# mrShark_08.net
KiCad netlist of a schematic drawn in EAGLE
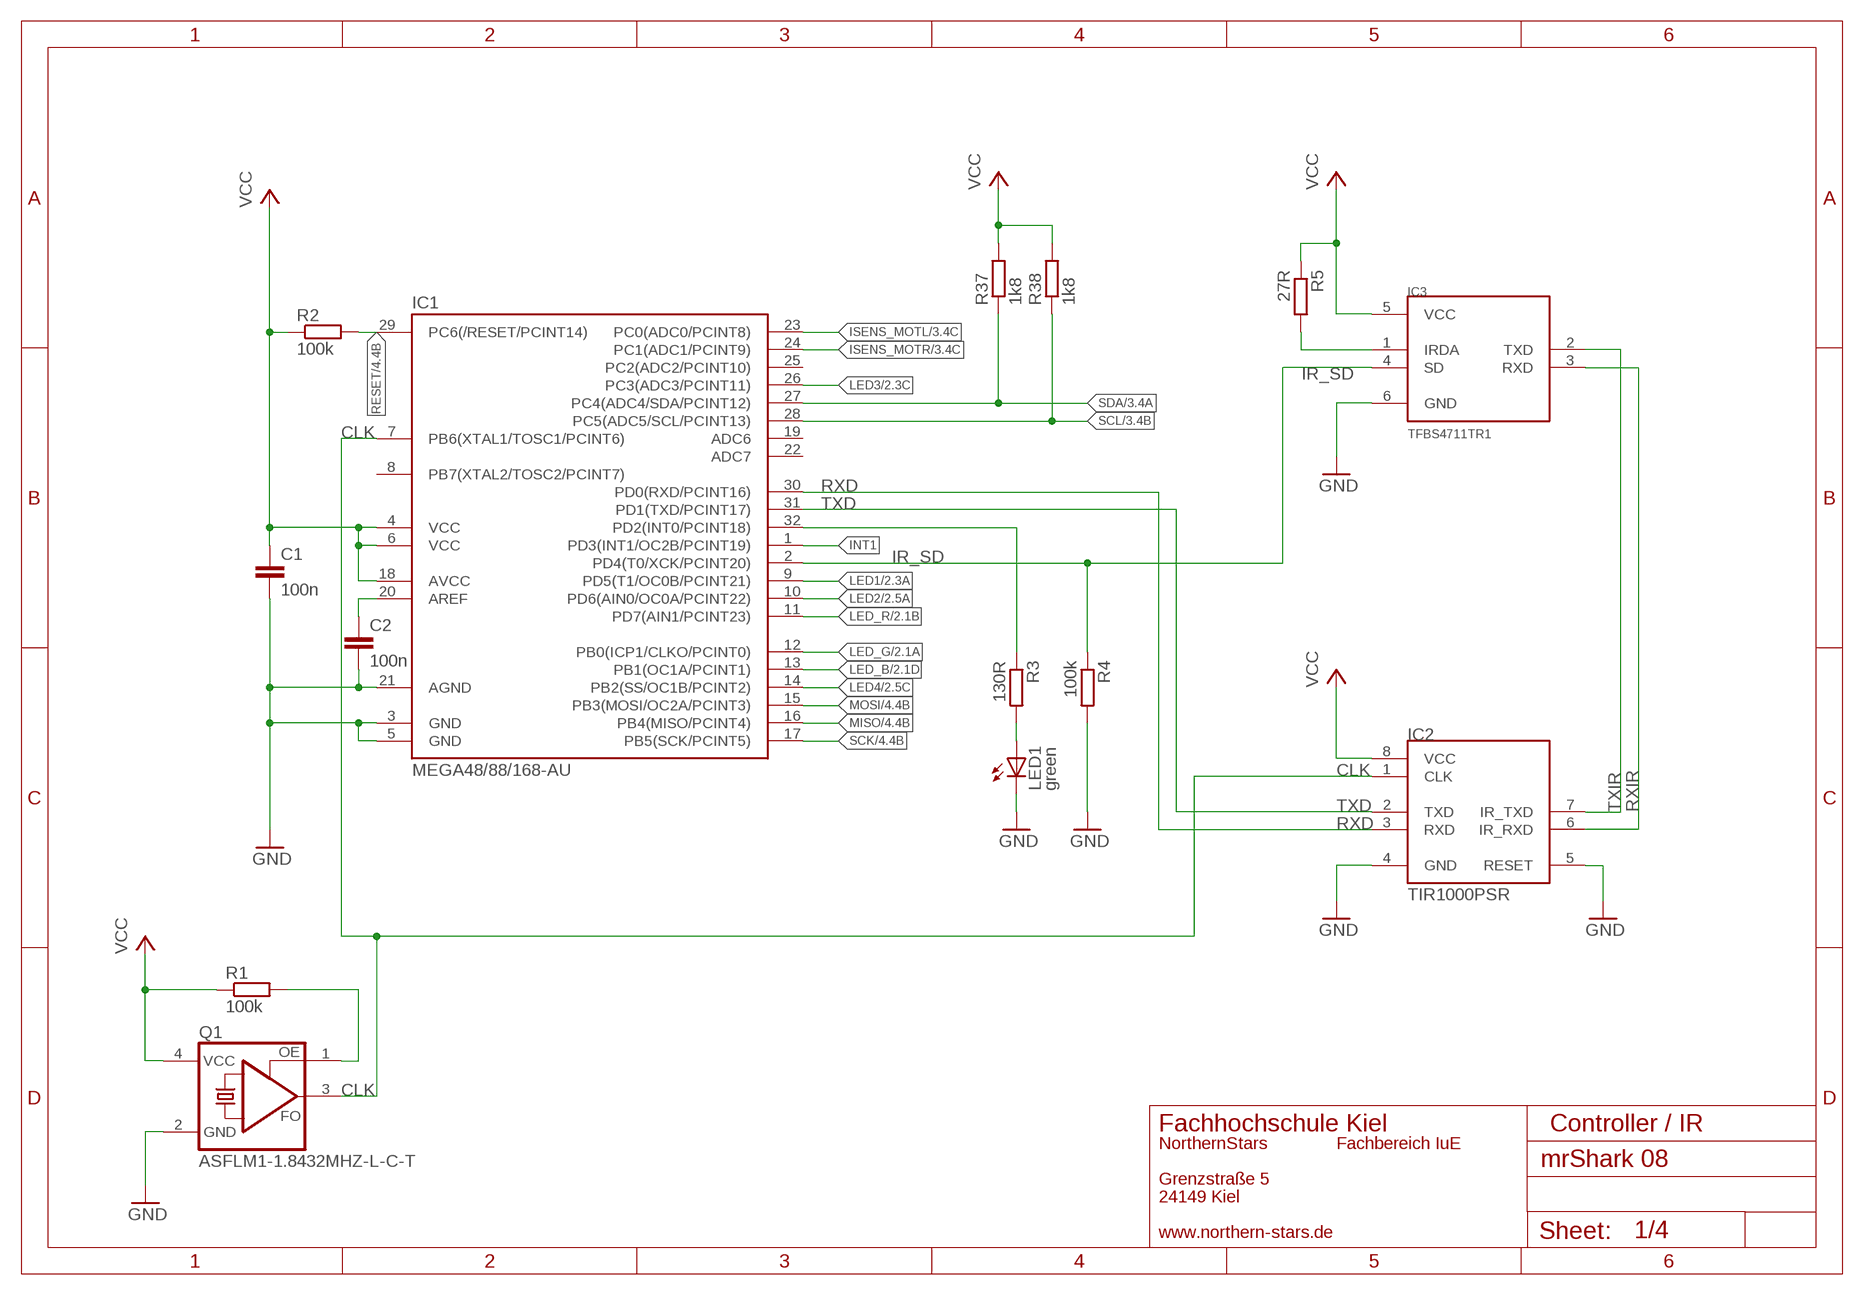
[diagram p0: schematic, sheet 1]
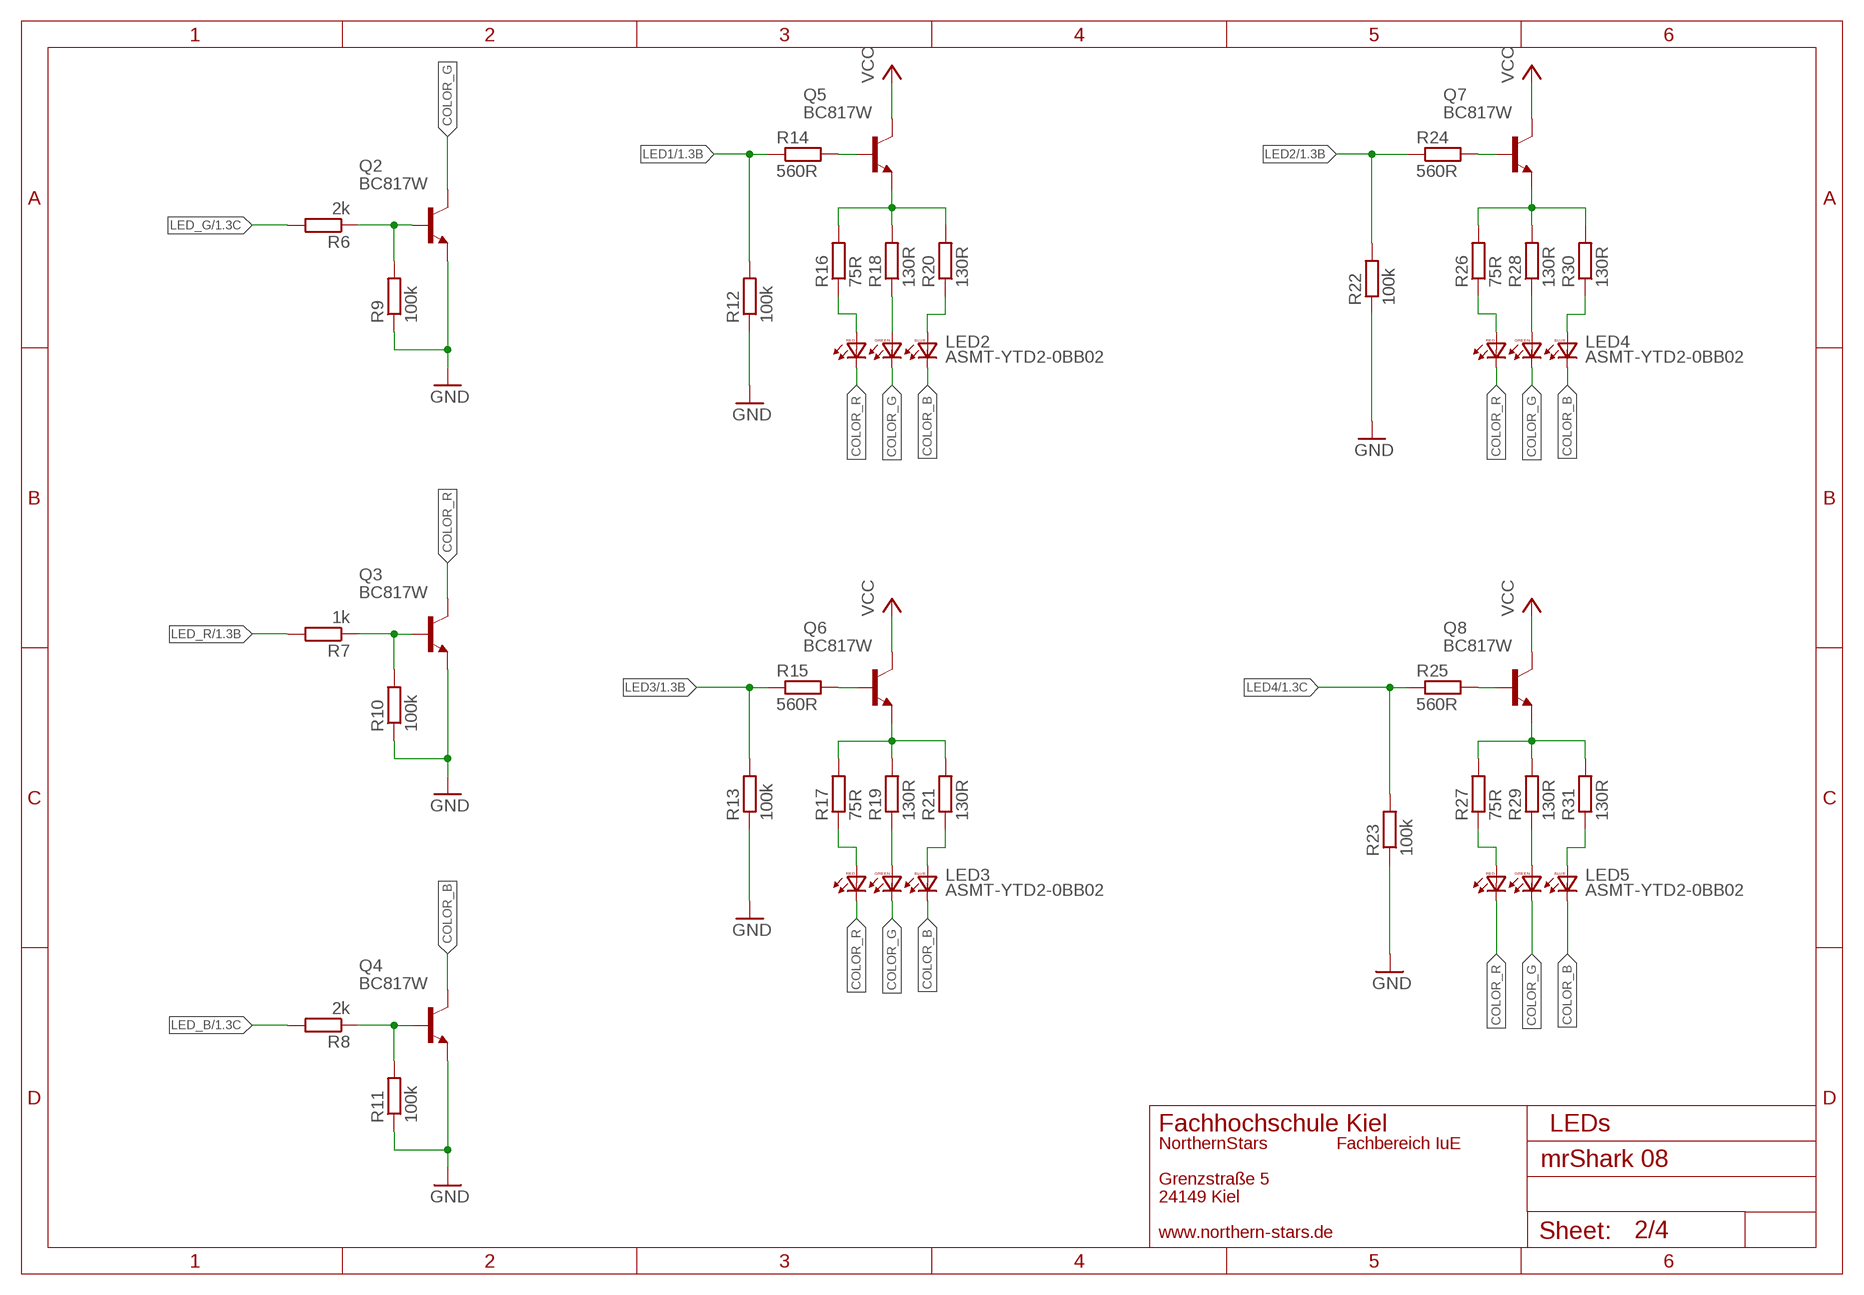
[diagram p1: schematic, sheet 2]
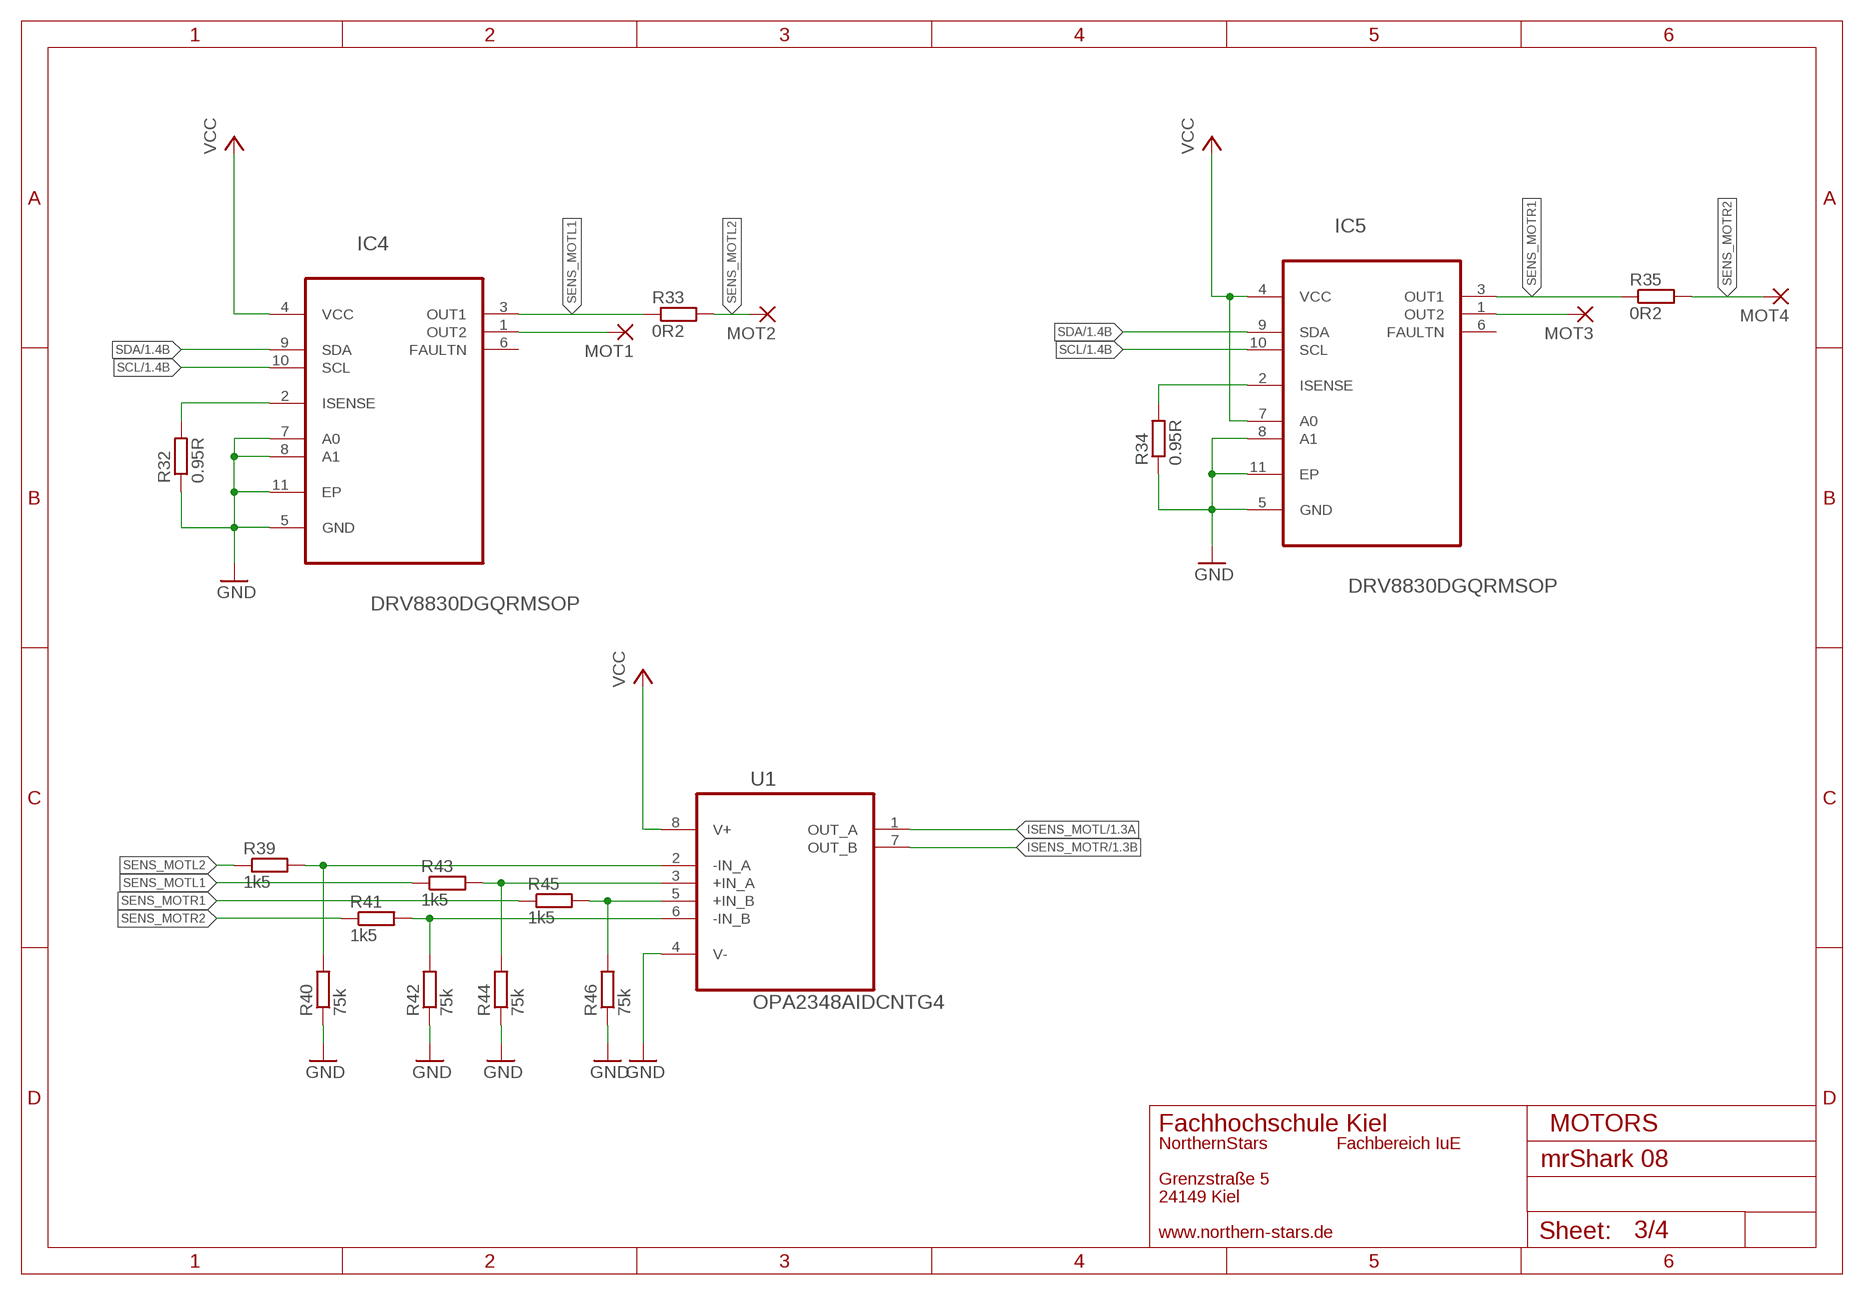
[diagram p2: schematic, sheet 3]
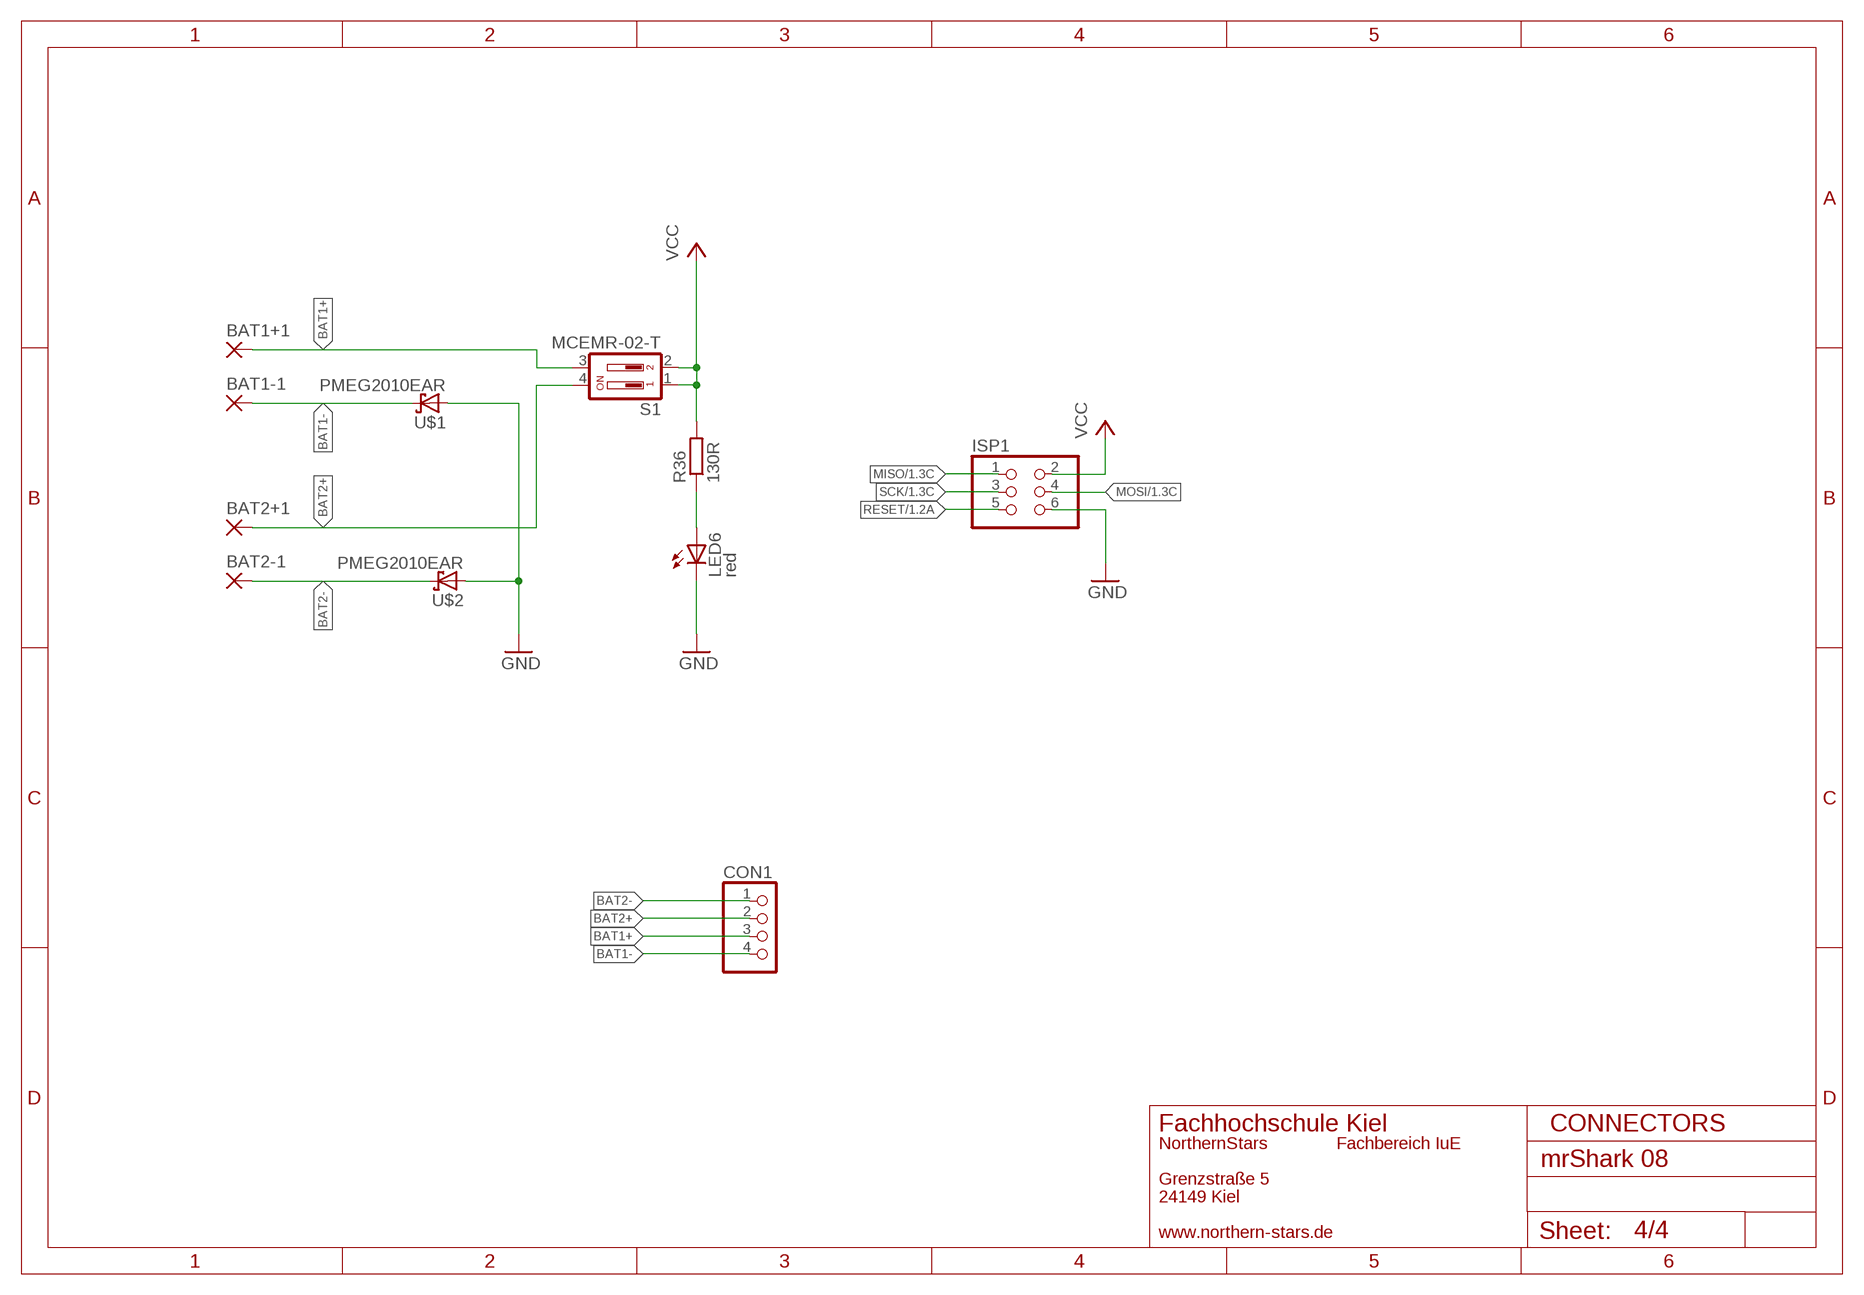
[diagram p3: schematic, sheet 4]

(export (version "E")
  (design (tool "Eeschema 10.0.6"))
  (components
    (comp (ref "IC4")
      (value "DRV8830DGQRMSOP")
      (footprint "eagle-import:SOP65P640X110-15N")
      (fields (field (name "MPN") "DRV8830DGQR"))
      (libsource (lib "eagle-import") (part "DRV8830DGQRMSOP"))
    )
    (comp (ref "IC5")
      (value "DRV8830DGQRMSOP")
      (footprint "eagle-import:SOP65P640X110-15N")
      (fields (field (name "MPN") "DRV8830DGQR"))
      (libsource (lib "eagle-import") (part "DRV8830DGQRMSOP"))
    )
    (comp (ref "MOT1")
      (value "1,6/0,9")
      (footprint "eagle-import:1,6_0,9")
      (libsource (lib "eagle-import") (part "1,6/0,9"))
    )
    (comp (ref "MOT2")
      (value "1,6/0,9")
      (footprint "eagle-import:1,6_0,9")
      (libsource (lib "eagle-import") (part "1,6/0,9"))
    )
    (comp (ref "MOT3")
      (value "1,6/0,9")
      (footprint "eagle-import:1,6_0,9")
      (libsource (lib "eagle-import") (part "1,6/0,9"))
    )
    (comp (ref "MOT4")
      (value "1,6/0,9")
      (footprint "eagle-import:1,6_0,9")
      (libsource (lib "eagle-import") (part "1,6/0,9"))
    )
    (comp (ref "R32")
      (value "0.95R")
      (footprint "eagle-import:R1206")
      (libsource (lib "eagle-import") (part "R-EU_R1206"))
    )
    (comp (ref "R33")
      (value "0R2")
      (footprint "eagle-import:R0805")
      (libsource (lib "eagle-import") (part "R-EU_R0805"))
    )
    (comp (ref "R34")
      (value "0.95R")
      (footprint "eagle-import:R1206")
      (libsource (lib "eagle-import") (part "R-EU_R1206"))
    )
    (comp (ref "R35")
      (value "0R2")
      (footprint "eagle-import:R0805")
      (libsource (lib "eagle-import") (part "R-EU_R0805"))
    )
    (comp (ref "R39")
      (value "1k5")
      (footprint "eagle-import:R1206")
      (libsource (lib "eagle-import") (part "R-EU_R1206"))
    )
    (comp (ref "R40")
      (value "75k")
      (footprint "eagle-import:R1206")
      (libsource (lib "eagle-import") (part "R-EU_R1206"))
    )
    (comp (ref "R41")
      (value "1k5")
      (footprint "eagle-import:R1206")
      (libsource (lib "eagle-import") (part "R-EU_R1206"))
    )
    (comp (ref "R42")
      (value "75k")
      (footprint "eagle-import:R1206")
      (libsource (lib "eagle-import") (part "R-EU_R1206"))
    )
    (comp (ref "R43")
      (value "1k5")
      (footprint "eagle-import:R1206")
      (libsource (lib "eagle-import") (part "R-EU_R1206"))
    )
    (comp (ref "R44")
      (value "75k")
      (footprint "eagle-import:R1206")
      (libsource (lib "eagle-import") (part "R-EU_R1206"))
    )
    (comp (ref "R45")
      (value "1k5")
      (footprint "eagle-import:R1206")
      (libsource (lib "eagle-import") (part "R-EU_R1206"))
    )
    (comp (ref "R46")
      (value "75k")
      (footprint "eagle-import:R1206")
      (libsource (lib "eagle-import") (part "R-EU_R1206"))
    )
    (comp (ref "U1")
      (value "OPA2348AIDCNTG4")
      (footprint "eagle-import:SOT65P280X145-8N")
      (libsource (lib "eagle-import") (part "OPA2348AIDCNTG4"))
    )
    (comp (ref "C1")
      (value "100n")
      (footprint "eagle-import:C0805")
      (libsource (lib "eagle-import") (part "C-EUC0805"))
    )
    (comp (ref "C2")
      (value "100n")
      (footprint "eagle-import:C0805")
      (libsource (lib "eagle-import") (part "C-EUC0805"))
    )
    (comp (ref "IC1")
      (value "MEGA48/88/168-AU")
      (footprint "eagle-import:TQFP32-08")
      (libsource (lib "eagle-import") (part "MEGA48/88/168-AU"))
    )
    (comp (ref "IC2")
      (value "TIR1000PSR")
      (footprint "eagle-import:SO-08")
      (libsource (lib "eagle-import") (part "TIR1000PSR"))
    )
    (comp (ref "IC3")
      (value "TFBS4711TR1")
      (footprint "eagle-import:TFBS4711")
      (libsource (lib "eagle-import") (part "TFBS4711TR1"))
    )
    (comp (ref "LED1")
      (value "green")
      (footprint "eagle-import:CHIPLED_1206")
      (libsource (lib "eagle-import") (part "LEDCHIPLED_1206"))
    )
    (comp (ref "Q1")
      (value "ASFLM1-1.8432MHZ-L-C-T")
      (footprint "eagle-import:HC736")
      (libsource (lib "eagle-import") (part "HC536(738)"))
    )
    (comp (ref "R1")
      (value "100k")
      (footprint "eagle-import:R1206")
      (libsource (lib "eagle-import") (part "R-EU_R1206"))
    )
    (comp (ref "R2")
      (value "100k")
      (footprint "eagle-import:R1206")
      (libsource (lib "eagle-import") (part "R-EU_R1206"))
    )
    (comp (ref "R3")
      (value "130R")
      (footprint "eagle-import:R1206")
      (libsource (lib "eagle-import") (part "R-EU_R1206"))
    )
    (comp (ref "R4")
      (value "100k")
      (footprint "eagle-import:R1206")
      (libsource (lib "eagle-import") (part "R-EU_R1206"))
    )
    (comp (ref "R5")
      (value "27R")
      (footprint "eagle-import:R1206")
      (libsource (lib "eagle-import") (part "R-EU_R1206"))
    )
    (comp (ref "R37")
      (value "1k8")
      (footprint "eagle-import:R1206")
      (libsource (lib "eagle-import") (part "R-EU_R1206"))
    )
    (comp (ref "R38")
      (value "1k8")
      (footprint "eagle-import:R1206")
      (libsource (lib "eagle-import") (part "R-EU_R1206"))
    )
    (comp (ref "LED2")
      (value "ASMT-YTD2-0BB02")
      (footprint "eagle-import:PLCC6K")
      (libsource (lib "eagle-import") (part "PLCC6K"))
    )
    (comp (ref "LED3")
      (value "ASMT-YTD2-0BB02")
      (footprint "eagle-import:PLCC6K")
      (libsource (lib "eagle-import") (part "PLCC6K"))
    )
    (comp (ref "LED4")
      (value "ASMT-YTD2-0BB02")
      (footprint "eagle-import:PLCC6K")
      (libsource (lib "eagle-import") (part "PLCC6K"))
    )
    (comp (ref "LED5")
      (value "ASMT-YTD2-0BB02")
      (footprint "eagle-import:PLCC6K")
      (libsource (lib "eagle-import") (part "PLCC6K"))
    )
    (comp (ref "Q2")
      (value "BC817W")
      (footprint "eagle-import:SOT323-BEC")
      (libsource (lib "eagle-import") (part "BC817W"))
    )
    (comp (ref "Q3")
      (value "BC817W")
      (footprint "eagle-import:SOT323-BEC")
      (libsource (lib "eagle-import") (part "BC817W"))
    )
    (comp (ref "Q4")
      (value "BC817W")
      (footprint "eagle-import:SOT323-BEC")
      (libsource (lib "eagle-import") (part "BC817W"))
    )
    (comp (ref "Q5")
      (value "BC817W")
      (footprint "eagle-import:SOT323-BEC")
      (libsource (lib "eagle-import") (part "BC817W"))
    )
    (comp (ref "Q6")
      (value "BC817W")
      (footprint "eagle-import:SOT323-BEC")
      (libsource (lib "eagle-import") (part "BC817W"))
    )
    (comp (ref "Q7")
      (value "BC817W")
      (footprint "eagle-import:SOT323-BEC")
      (libsource (lib "eagle-import") (part "BC817W"))
    )
    (comp (ref "Q8")
      (value "BC817W")
      (footprint "eagle-import:SOT323-BEC")
      (libsource (lib "eagle-import") (part "BC817W"))
    )
    (comp (ref "R6")
      (value "2k")
      (footprint "eagle-import:R1206")
      (libsource (lib "eagle-import") (part "R-EU_R1206"))
    )
    (comp (ref "R7")
      (value "1k")
      (footprint "eagle-import:R1206")
      (libsource (lib "eagle-import") (part "R-EU_R1206"))
    )
    (comp (ref "R8")
      (value "2k")
      (footprint "eagle-import:R1206")
      (libsource (lib "eagle-import") (part "R-EU_R1206"))
    )
    (comp (ref "R9")
      (value "100k")
      (footprint "eagle-import:R1206")
      (libsource (lib "eagle-import") (part "R-EU_R1206"))
    )
    (comp (ref "R10")
      (value "100k")
      (footprint "eagle-import:R1206")
      (libsource (lib "eagle-import") (part "R-EU_R1206"))
    )
    (comp (ref "R11")
      (value "100k")
      (footprint "eagle-import:R1206")
      (libsource (lib "eagle-import") (part "R-EU_R1206"))
    )
    (comp (ref "R12")
      (value "100k")
      (footprint "eagle-import:R1206")
      (libsource (lib "eagle-import") (part "R-EU_R1206"))
    )
    (comp (ref "R13")
      (value "100k")
      (footprint "eagle-import:R1206")
      (libsource (lib "eagle-import") (part "R-EU_R1206"))
    )
    (comp (ref "R14")
      (value "560R")
      (footprint "eagle-import:R1206")
      (libsource (lib "eagle-import") (part "R-EU_R1206"))
    )
    (comp (ref "R15")
      (value "560R")
      (footprint "eagle-import:R1206")
      (libsource (lib "eagle-import") (part "R-EU_R1206"))
    )
    (comp (ref "R16")
      (value "75R")
      (footprint "eagle-import:R1206")
      (libsource (lib "eagle-import") (part "R-EU_R1206"))
    )
    (comp (ref "R17")
      (value "75R")
      (footprint "eagle-import:R1206")
      (libsource (lib "eagle-import") (part "R-EU_R1206"))
    )
    (comp (ref "R18")
      (value "130R")
      (footprint "eagle-import:R1206")
      (libsource (lib "eagle-import") (part "R-EU_R1206"))
    )
    (comp (ref "R19")
      (value "130R")
      (footprint "eagle-import:R1206")
      (libsource (lib "eagle-import") (part "R-EU_R1206"))
    )
    (comp (ref "R20")
      (value "130R")
      (footprint "eagle-import:R1206")
      (libsource (lib "eagle-import") (part "R-EU_R1206"))
    )
    (comp (ref "R21")
      (value "130R")
      (footprint "eagle-import:R1206")
      (libsource (lib "eagle-import") (part "R-EU_R1206"))
    )
    (comp (ref "R22")
      (value "100k")
      (footprint "eagle-import:R1206")
      (libsource (lib "eagle-import") (part "R-EU_R1206"))
    )
    (comp (ref "R23")
      (value "100k")
      (footprint "eagle-import:R1206")
      (libsource (lib "eagle-import") (part "R-EU_R1206"))
    )
    (comp (ref "R24")
      (value "560R")
      (footprint "eagle-import:R1206")
      (libsource (lib "eagle-import") (part "R-EU_R1206"))
    )
    (comp (ref "R25")
      (value "560R")
      (footprint "eagle-import:R1206")
      (libsource (lib "eagle-import") (part "R-EU_R1206"))
    )
    (comp (ref "R26")
      (value "75R")
      (footprint "eagle-import:R1206")
      (libsource (lib "eagle-import") (part "R-EU_R1206"))
    )
    (comp (ref "R27")
      (value "75R")
      (footprint "eagle-import:R1206")
      (libsource (lib "eagle-import") (part "R-EU_R1206"))
    )
    (comp (ref "R28")
      (value "130R")
      (footprint "eagle-import:R1206")
      (libsource (lib "eagle-import") (part "R-EU_R1206"))
    )
    (comp (ref "R29")
      (value "130R")
      (footprint "eagle-import:R1206")
      (libsource (lib "eagle-import") (part "R-EU_R1206"))
    )
    (comp (ref "R30")
      (value "130R")
      (footprint "eagle-import:R1206")
      (libsource (lib "eagle-import") (part "R-EU_R1206"))
    )
    (comp (ref "R31")
      (value "130R")
      (footprint "eagle-import:R1206")
      (libsource (lib "eagle-import") (part "R-EU_R1206"))
    )
    (comp (ref "BAT1+1")
      (value "1,6/0,9")
      (footprint "eagle-import:1,6_0,9")
      (libsource (lib "eagle-import") (part "1,6/0,9"))
    )
    (comp (ref "BAT1-1")
      (value "1,6/0,9")
      (footprint "eagle-import:1,6_0,9")
      (libsource (lib "eagle-import") (part "1,6/0,9"))
    )
    (comp (ref "BAT2+1")
      (value "1,6/0,9")
      (footprint "eagle-import:1,6_0,9")
      (libsource (lib "eagle-import") (part "1,6/0,9"))
    )
    (comp (ref "BAT2-1")
      (value "1,6/0,9")
      (footprint "eagle-import:1,6_0,9")
      (libsource (lib "eagle-import") (part "1,6/0,9"))
    )
    (comp (ref "CON1")
      (value "PINHD-1X04_2.54-SMD-90°")
      (footprint "eagle-import:1X04SMD_90")
      (libsource (lib "eagle-import") (part "PINHD-1X04_2.54-SMD-90°"))
    )
    (comp (ref "ISP1")
      (value "PINHD-2X03_2.54-SMD")
      (footprint "eagle-import:2X03SMD")
      (libsource (lib "eagle-import") (part "PINHD-2X03_2.54-SMD"))
    )
    (comp (ref "LED6")
      (value "red")
      (footprint "eagle-import:CHIPLED_1206")
      (libsource (lib "eagle-import") (part "LEDCHIPLED_1206"))
    )
    (comp (ref "R36")
      (value "130R")
      (footprint "eagle-import:R1206")
      (libsource (lib "eagle-import") (part "R-EU_R1206"))
    )
    (comp (ref "S1")
      (value "MCEMR-02-T")
      (footprint "eagle-import:CTS-219-02")
      (libsource (lib "eagle-import") (part "219-02"))
    )
    (comp (ref "U$1")
      (value "PMEG2010EAR")
      (footprint "eagle-import:SOD323-R")
      (libsource (lib "eagle-import") (part "PMEG2010EAR"))
    )
    (comp (ref "U$2")
      (value "PMEG2010EAR")
      (footprint "eagle-import:SOD323-R")
      (libsource (lib "eagle-import") (part "PMEG2010EAR"))
    )
  )
  (nets
    (net (code "1") (name "BAT1+") (class "Default")
      (node (ref "BAT1+1") (pin "1") (pinfunction "P_1") (pintype "passive"))
      (node (ref "CON1") (pin "3") (pinfunction "3_3") (pintype "passive"))
      (node (ref "S1") (pin "3") (pinfunction "3_3") (pintype "passive"))
    )
    (net (code "2") (name "BAT1-") (class "Default")
      (node (ref "BAT1-1") (pin "1") (pinfunction "P_1") (pintype "passive"))
      (node (ref "CON1") (pin "4") (pinfunction "4_4") (pintype "passive"))
      (node (ref "U$1") (pin "C") (pinfunction "C_C") (pintype "passive"))
    )
    (net (code "3") (name "BAT2+") (class "Default")
      (node (ref "BAT2+1") (pin "1") (pinfunction "P_1") (pintype "passive"))
      (node (ref "CON1") (pin "2") (pinfunction "2_2") (pintype "passive"))
      (node (ref "S1") (pin "4") (pinfunction "4_4") (pintype "passive"))
    )
    (net (code "4") (name "BAT2-") (class "Default")
      (node (ref "BAT2-1") (pin "1") (pinfunction "P_1") (pintype "passive"))
      (node (ref "CON1") (pin "1") (pinfunction "1_1") (pintype "passive"))
      (node (ref "U$2") (pin "C") (pinfunction "C_C") (pintype "passive"))
    )
    (net (code "5") (name "CLK") (class "Default")
      (node (ref "IC1") (pin "7") (pinfunction "PB6(XTAL1/TOSC1/PCINT6)_7") (pintype "bidirectional"))
      (node (ref "IC2") (pin "1") (pinfunction "CLK_1") (pintype "bidirectional"))
      (node (ref "Q1") (pin "3") (pinfunction "FO_3") (pintype "output"))
    )
    (net (code "6") (name "COLOR_B") (class "Default")
      (node (ref "LED2") (pin "1") (pinfunction "BC_1") (pintype "passive"))
      (node (ref "LED3") (pin "1") (pinfunction "BC_1") (pintype "passive"))
      (node (ref "LED4") (pin "1") (pinfunction "BC_1") (pintype "passive"))
      (node (ref "LED5") (pin "1") (pinfunction "BC_1") (pintype "passive"))
      (node (ref "Q4") (pin "C") (pinfunction "C_C") (pintype "passive"))
    )
    (net (code "7") (name "COLOR_G") (class "Default")
      (node (ref "LED2") (pin "2") (pinfunction "GC_2") (pintype "passive"))
      (node (ref "LED3") (pin "2") (pinfunction "GC_2") (pintype "passive"))
      (node (ref "LED4") (pin "2") (pinfunction "GC_2") (pintype "passive"))
      (node (ref "LED5") (pin "2") (pinfunction "GC_2") (pintype "passive"))
      (node (ref "Q2") (pin "C") (pinfunction "C_C") (pintype "passive"))
    )
    (net (code "8") (name "COLOR_R") (class "Default")
      (node (ref "LED2") (pin "3") (pinfunction "RC_3") (pintype "passive"))
      (node (ref "LED3") (pin "3") (pinfunction "RC_3") (pintype "passive"))
      (node (ref "LED4") (pin "3") (pinfunction "RC_3") (pintype "passive"))
      (node (ref "LED5") (pin "3") (pinfunction "RC_3") (pintype "passive"))
      (node (ref "Q3") (pin "C") (pinfunction "C_C") (pintype "passive"))
    )
    (net (code "9") (name "GND") (class "Default")
      (node (ref "C1") (pin "2") (pinfunction "2_2") (pintype "passive"))
      (node (ref "C2") (pin "2") (pinfunction "2_2") (pintype "passive"))
      (node (ref "IC1") (pin "21") (pinfunction "AGND_21") (pintype "power_in"))
      (node (ref "IC1") (pin "3") (pinfunction "GND_3") (pintype "power_in"))
      (node (ref "IC1") (pin "5") (pinfunction "GND_5") (pintype "power_in"))
      (node (ref "IC2") (pin "4") (pinfunction "GND_4") (pintype "bidirectional"))
      (node (ref "IC2") (pin "5") (pinfunction "RESET_5") (pintype "bidirectional"))
      (node (ref "IC3") (pin "6") (pinfunction "GND_6") (pintype "bidirectional"))
      (node (ref "IC4") (pin "11") (pinfunction "EP_11") (pintype "passive"))
      (node (ref "IC4") (pin "5") (pinfunction "GND_5") (pintype "passive"))
      (node (ref "IC4") (pin "7") (pinfunction "A0_7") (pintype "input"))
      (node (ref "IC4") (pin "8") (pinfunction "A1_8") (pintype "input"))
      (node (ref "IC5") (pin "11") (pinfunction "EP_11") (pintype "passive"))
      (node (ref "IC5") (pin "5") (pinfunction "GND_5") (pintype "passive"))
      (node (ref "IC5") (pin "8") (pinfunction "A1_8") (pintype "input"))
      (node (ref "ISP1") (pin "6") (pinfunction "6_6") (pintype "passive"))
      (node (ref "LED1") (pin "C") (pinfunction "C_C") (pintype "passive"))
      (node (ref "LED6") (pin "C") (pinfunction "C_C") (pintype "passive"))
      (node (ref "Q1") (pin "2") (pinfunction "GND_2") (pintype "power_in"))
      (node (ref "Q2") (pin "E") (pinfunction "E_E") (pintype "passive"))
      (node (ref "Q3") (pin "E") (pinfunction "E_E") (pintype "passive"))
      (node (ref "Q4") (pin "E") (pinfunction "E_E") (pintype "passive"))
      (node (ref "R10") (pin "1") (pinfunction "1_1") (pintype "passive"))
      (node (ref "R11") (pin "1") (pinfunction "1_1") (pintype "passive"))
      (node (ref "R12") (pin "1") (pinfunction "1_1") (pintype "passive"))
      (node (ref "R13") (pin "1") (pinfunction "1_1") (pintype "passive"))
      (node (ref "R22") (pin "1") (pinfunction "1_1") (pintype "passive"))
      (node (ref "R23") (pin "1") (pinfunction "1_1") (pintype "passive"))
      (node (ref "R32") (pin "1") (pinfunction "1_1") (pintype "passive"))
      (node (ref "R34") (pin "1") (pinfunction "1_1") (pintype "passive"))
      (node (ref "R4") (pin "2") (pinfunction "2_2") (pintype "passive"))
      (node (ref "R40") (pin "1") (pinfunction "1_1") (pintype "passive"))
      (node (ref "R42") (pin "1") (pinfunction "1_1") (pintype "passive"))
      (node (ref "R44") (pin "1") (pinfunction "1_1") (pintype "passive"))
      (node (ref "R46") (pin "1") (pinfunction "1_1") (pintype "passive"))
      (node (ref "R9") (pin "1") (pinfunction "1_1") (pintype "passive"))
      (node (ref "U$1") (pin "A") (pinfunction "A_A") (pintype "passive"))
      (node (ref "U$2") (pin "A") (pinfunction "A_A") (pintype "passive"))
      (node (ref "U1") (pin "4") (pinfunction "V-_4") (pintype "power_in"))
    )
    (net (code "10") (name "INT1") (class "Default")
      (node (ref "IC1") (pin "1") (pinfunction "PD3(INT1/OC2B/PCINT19)_1") (pintype "bidirectional"))
    )
    (net (code "11") (name "IR_SD") (class "Default")
      (node (ref "IC1") (pin "2") (pinfunction "PD4(T0/XCK/PCINT20)_2") (pintype "bidirectional"))
      (node (ref "IC3") (pin "4") (pinfunction "SD_4") (pintype "bidirectional"))
      (node (ref "R4") (pin "1") (pinfunction "1_1") (pintype "passive"))
    )
    (net (code "12") (name "ISENS_MOTL") (class "Default")
      (node (ref "IC1") (pin "23") (pinfunction "PC0(ADC0/PCINT8)_23") (pintype "bidirectional"))
      (node (ref "U1") (pin "1") (pinfunction "OUT_A_1") (pintype "output"))
    )
    (net (code "13") (name "ISENS_MOTR") (class "Default")
      (node (ref "IC1") (pin "24") (pinfunction "PC1(ADC1/PCINT9)_24") (pintype "bidirectional"))
      (node (ref "U1") (pin "7") (pinfunction "OUT_B_7") (pintype "output"))
    )
    (net (code "14") (name "LED1") (class "Default")
      (node (ref "IC1") (pin "9") (pinfunction "PD5(T1/OC0B/PCINT21)_9") (pintype "bidirectional"))
      (node (ref "R12") (pin "2") (pinfunction "2_2") (pintype "passive"))
      (node (ref "R14") (pin "1") (pinfunction "1_1") (pintype "passive"))
    )
    (net (code "15") (name "LED2") (class "Default")
      (node (ref "IC1") (pin "10") (pinfunction "PD6(AIN0/OC0A/PCINT22)_10") (pintype "bidirectional"))
      (node (ref "R22") (pin "2") (pinfunction "2_2") (pintype "passive"))
      (node (ref "R24") (pin "1") (pinfunction "1_1") (pintype "passive"))
    )
    (net (code "16") (name "LED3") (class "Default")
      (node (ref "IC1") (pin "26") (pinfunction "PC3(ADC3/PCINT11)_26") (pintype "bidirectional"))
      (node (ref "R13") (pin "2") (pinfunction "2_2") (pintype "passive"))
      (node (ref "R15") (pin "1") (pinfunction "1_1") (pintype "passive"))
    )
    (net (code "17") (name "LED4") (class "Default")
      (node (ref "IC1") (pin "14") (pinfunction "PB2(SS/OC1B/PCINT2)_14") (pintype "bidirectional"))
      (node (ref "R23") (pin "2") (pinfunction "2_2") (pintype "passive"))
      (node (ref "R25") (pin "1") (pinfunction "1_1") (pintype "passive"))
    )
    (net (code "18") (name "LED_B") (class "Default")
      (node (ref "IC1") (pin "13") (pinfunction "PB1(OC1A/PCINT1)_13") (pintype "bidirectional"))
      (node (ref "R8") (pin "2") (pinfunction "2_2") (pintype "passive"))
    )
    (net (code "19") (name "LED_G") (class "Default")
      (node (ref "IC1") (pin "12") (pinfunction "PB0(ICP1/CLKO/PCINT0)_12") (pintype "bidirectional"))
      (node (ref "R6") (pin "2") (pinfunction "2_2") (pintype "passive"))
    )
    (net (code "20") (name "LED_R") (class "Default")
      (node (ref "IC1") (pin "11") (pinfunction "PD7(AIN1/PCINT23)_11") (pintype "bidirectional"))
      (node (ref "R7") (pin "2") (pinfunction "2_2") (pintype "passive"))
    )
    (net (code "21") (name "MISO") (class "Default")
      (node (ref "IC1") (pin "16") (pinfunction "PB4(MISO/PCINT4)_16") (pintype "bidirectional"))
      (node (ref "ISP1") (pin "1") (pinfunction "1_1") (pintype "passive"))
    )
    (net (code "22") (name "MOSI") (class "Default")
      (node (ref "IC1") (pin "15") (pinfunction "PB3(MOSI/OC2A/PCINT3)_15") (pintype "bidirectional"))
      (node (ref "ISP1") (pin "4") (pinfunction "4_4") (pintype "passive"))
    )
    (net (code "23") (name "Net-(IC1-AREF)") (class "Default")
      (node (ref "C2") (pin "1") (pinfunction "1_1") (pintype "passive"))
      (node (ref "IC1") (pin "20") (pinfunction "AREF_20") (pintype "passive"))
    )
    (net (code "24") (name "Net-(IC1-PD2(INT0{slash}PCINT18))") (class "Default")
      (node (ref "IC1") (pin "32") (pinfunction "PD2(INT0/PCINT18)_32") (pintype "bidirectional"))
      (node (ref "R3") (pin "1") (pinfunction "1_1") (pintype "passive"))
    )
    (net (code "25") (name "Net-(IC3-IRDA)") (class "Default")
      (node (ref "IC3") (pin "1") (pinfunction "IRDA_1") (pintype "bidirectional"))
      (node (ref "R5") (pin "2") (pinfunction "2_2") (pintype "passive"))
    )
    (net (code "26") (name "Net-(IC4-ISENSE)") (class "Default")
      (node (ref "IC4") (pin "2") (pinfunction "ISENSE_2") (pintype "input"))
      (node (ref "R32") (pin "2") (pinfunction "2_2") (pintype "passive"))
    )
    (net (code "27") (name "Net-(IC4-OUT2)") (class "Default")
      (node (ref "IC4") (pin "1") (pinfunction "OUT2_1") (pintype "output"))
      (node (ref "MOT1") (pin "1") (pinfunction "P_1") (pintype "passive"))
    )
    (net (code "28") (name "Net-(IC5-ISENSE)") (class "Default")
      (node (ref "IC5") (pin "2") (pinfunction "ISENSE_2") (pintype "input"))
      (node (ref "R34") (pin "2") (pinfunction "2_2") (pintype "passive"))
    )
    (net (code "29") (name "Net-(IC5-OUT2)") (class "Default")
      (node (ref "IC5") (pin "1") (pinfunction "OUT2_1") (pintype "output"))
      (node (ref "MOT3") (pin "1") (pinfunction "P_1") (pintype "passive"))
    )
    (net (code "30") (name "Net-(LED1-PadA)") (class "Default")
      (node (ref "LED1") (pin "A") (pinfunction "A_A") (pintype "passive"))
      (node (ref "R3") (pin "2") (pinfunction "2_2") (pintype "passive"))
    )
    (net (code "31") (name "Net-(LED2-BA)") (class "Default")
      (node (ref "LED2") (pin "6") (pinfunction "BA_6") (pintype "passive"))
      (node (ref "R20") (pin "1") (pinfunction "1_1") (pintype "passive"))
    )
    (net (code "32") (name "Net-(LED2-GA)") (class "Default")
      (node (ref "LED2") (pin "5") (pinfunction "GA_5") (pintype "passive"))
      (node (ref "R18") (pin "1") (pinfunction "1_1") (pintype "passive"))
    )
    (net (code "33") (name "Net-(LED2-RA)") (class "Default")
      (node (ref "LED2") (pin "4") (pinfunction "RA_4") (pintype "passive"))
      (node (ref "R16") (pin "1") (pinfunction "1_1") (pintype "passive"))
    )
    (net (code "34") (name "Net-(LED3-BA)") (class "Default")
      (node (ref "LED3") (pin "6") (pinfunction "BA_6") (pintype "passive"))
      (node (ref "R21") (pin "1") (pinfunction "1_1") (pintype "passive"))
    )
    (net (code "35") (name "Net-(LED3-GA)") (class "Default")
      (node (ref "LED3") (pin "5") (pinfunction "GA_5") (pintype "passive"))
      (node (ref "R19") (pin "1") (pinfunction "1_1") (pintype "passive"))
    )
    (net (code "36") (name "Net-(LED3-RA)") (class "Default")
      (node (ref "LED3") (pin "4") (pinfunction "RA_4") (pintype "passive"))
      (node (ref "R17") (pin "1") (pinfunction "1_1") (pintype "passive"))
    )
    (net (code "37") (name "Net-(LED4-BA)") (class "Default")
      (node (ref "LED4") (pin "6") (pinfunction "BA_6") (pintype "passive"))
      (node (ref "R30") (pin "1") (pinfunction "1_1") (pintype "passive"))
    )
    (net (code "38") (name "Net-(LED4-GA)") (class "Default")
      (node (ref "LED4") (pin "5") (pinfunction "GA_5") (pintype "passive"))
      (node (ref "R28") (pin "1") (pinfunction "1_1") (pintype "passive"))
    )
    (net (code "39") (name "Net-(LED4-RA)") (class "Default")
      (node (ref "LED4") (pin "4") (pinfunction "RA_4") (pintype "passive"))
      (node (ref "R26") (pin "1") (pinfunction "1_1") (pintype "passive"))
    )
    (net (code "40") (name "Net-(LED5-BA)") (class "Default")
      (node (ref "LED5") (pin "6") (pinfunction "BA_6") (pintype "passive"))
      (node (ref "R31") (pin "1") (pinfunction "1_1") (pintype "passive"))
    )
    (net (code "41") (name "Net-(LED5-GA)") (class "Default")
      (node (ref "LED5") (pin "5") (pinfunction "GA_5") (pintype "passive"))
      (node (ref "R29") (pin "1") (pinfunction "1_1") (pintype "passive"))
    )
    (net (code "42") (name "Net-(LED5-RA)") (class "Default")
      (node (ref "LED5") (pin "4") (pinfunction "RA_4") (pintype "passive"))
      (node (ref "R27") (pin "1") (pinfunction "1_1") (pintype "passive"))
    )
    (net (code "43") (name "Net-(LED6-PadA)") (class "Default")
      (node (ref "LED6") (pin "A") (pinfunction "A_A") (pintype "passive"))
      (node (ref "R36") (pin "1") (pinfunction "1_1") (pintype "passive"))
    )
    (net (code "44") (name "Net-(Q1-OE)") (class "Default")
      (node (ref "Q1") (pin "1") (pinfunction "OE_1") (pintype "input"))
      (node (ref "R1") (pin "2") (pinfunction "2_2") (pintype "passive"))
    )
    (net (code "45") (name "Net-(Q2-PadB)") (class "Default")
      (node (ref "Q2") (pin "B") (pinfunction "B_B") (pintype "passive"))
      (node (ref "R6") (pin "1") (pinfunction "1_1") (pintype "passive"))
      (node (ref "R9") (pin "2") (pinfunction "2_2") (pintype "passive"))
    )
    (net (code "46") (name "Net-(Q3-PadB)") (class "Default")
      (node (ref "Q3") (pin "B") (pinfunction "B_B") (pintype "passive"))
      (node (ref "R10") (pin "2") (pinfunction "2_2") (pintype "passive"))
      (node (ref "R7") (pin "1") (pinfunction "1_1") (pintype "passive"))
    )
    (net (code "47") (name "Net-(Q4-PadB)") (class "Default")
      (node (ref "Q4") (pin "B") (pinfunction "B_B") (pintype "passive"))
      (node (ref "R11") (pin "2") (pinfunction "2_2") (pintype "passive"))
      (node (ref "R8") (pin "1") (pinfunction "1_1") (pintype "passive"))
    )
    (net (code "48") (name "Net-(Q5-PadB)") (class "Default")
      (node (ref "Q5") (pin "B") (pinfunction "B_B") (pintype "passive"))
      (node (ref "R14") (pin "2") (pinfunction "2_2") (pintype "passive"))
    )
    (net (code "49") (name "Net-(Q5-PadE)") (class "Default")
      (node (ref "Q5") (pin "E") (pinfunction "E_E") (pintype "passive"))
      (node (ref "R16") (pin "2") (pinfunction "2_2") (pintype "passive"))
      (node (ref "R18") (pin "2") (pinfunction "2_2") (pintype "passive"))
      (node (ref "R20") (pin "2") (pinfunction "2_2") (pintype "passive"))
    )
    (net (code "50") (name "Net-(Q6-PadB)") (class "Default")
      (node (ref "Q6") (pin "B") (pinfunction "B_B") (pintype "passive"))
      (node (ref "R15") (pin "2") (pinfunction "2_2") (pintype "passive"))
    )
    (net (code "51") (name "Net-(Q6-PadE)") (class "Default")
      (node (ref "Q6") (pin "E") (pinfunction "E_E") (pintype "passive"))
      (node (ref "R17") (pin "2") (pinfunction "2_2") (pintype "passive"))
      (node (ref "R19") (pin "2") (pinfunction "2_2") (pintype "passive"))
      (node (ref "R21") (pin "2") (pinfunction "2_2") (pintype "passive"))
    )
    (net (code "52") (name "Net-(Q7-PadB)") (class "Default")
      (node (ref "Q7") (pin "B") (pinfunction "B_B") (pintype "passive"))
      (node (ref "R24") (pin "2") (pinfunction "2_2") (pintype "passive"))
    )
    (net (code "53") (name "Net-(Q7-PadE)") (class "Default")
      (node (ref "Q7") (pin "E") (pinfunction "E_E") (pintype "passive"))
      (node (ref "R26") (pin "2") (pinfunction "2_2") (pintype "passive"))
      (node (ref "R28") (pin "2") (pinfunction "2_2") (pintype "passive"))
      (node (ref "R30") (pin "2") (pinfunction "2_2") (pintype "passive"))
    )
    (net (code "54") (name "Net-(Q8-PadB)") (class "Default")
      (node (ref "Q8") (pin "B") (pinfunction "B_B") (pintype "passive"))
      (node (ref "R25") (pin "2") (pinfunction "2_2") (pintype "passive"))
    )
    (net (code "55") (name "Net-(Q8-PadE)") (class "Default")
      (node (ref "Q8") (pin "E") (pinfunction "E_E") (pintype "passive"))
      (node (ref "R27") (pin "2") (pinfunction "2_2") (pintype "passive"))
      (node (ref "R29") (pin "2") (pinfunction "2_2") (pintype "passive"))
      (node (ref "R31") (pin "2") (pinfunction "2_2") (pintype "passive"))
    )
    (net (code "56") (name "Net-(U1-+IN_A)") (class "Default")
      (node (ref "R43") (pin "2") (pinfunction "2_2") (pintype "passive"))
      (node (ref "R44") (pin "2") (pinfunction "2_2") (pintype "passive"))
      (node (ref "U1") (pin "3") (pinfunction "+IN_A_3") (pintype "input"))
    )
    (net (code "57") (name "Net-(U1-+IN_B)") (class "Default")
      (node (ref "R45") (pin "2") (pinfunction "2_2") (pintype "passive"))
      (node (ref "R46") (pin "2") (pinfunction "2_2") (pintype "passive"))
      (node (ref "U1") (pin "5") (pinfunction "+IN_B_5") (pintype "input"))
    )
    (net (code "58") (name "Net-(U1--IN_A)") (class "Default")
      (node (ref "R39") (pin "2") (pinfunction "2_2") (pintype "passive"))
      (node (ref "R40") (pin "2") (pinfunction "2_2") (pintype "passive"))
      (node (ref "U1") (pin "2") (pinfunction "-IN_A_2") (pintype "input"))
    )
    (net (code "59") (name "Net-(U1--IN_B)") (class "Default")
      (node (ref "R41") (pin "2") (pinfunction "2_2") (pintype "passive"))
      (node (ref "R42") (pin "2") (pinfunction "2_2") (pintype "passive"))
      (node (ref "U1") (pin "6") (pinfunction "-IN_B_6") (pintype "input"))
    )
    (net (code "60") (name "RESET") (class "Default")
      (node (ref "IC1") (pin "29") (pinfunction "PC6(/RESET/PCINT14)_29") (pintype "bidirectional"))
      (node (ref "ISP1") (pin "5") (pinfunction "5_5") (pintype "passive"))
      (node (ref "R2") (pin "2") (pinfunction "2_2") (pintype "passive"))
    )
    (net (code "61") (name "RXD") (class "Default")
      (node (ref "IC1") (pin "30") (pinfunction "PD0(RXD/PCINT16)_30") (pintype "bidirectional"))
      (node (ref "IC2") (pin "3") (pinfunction "RXD_3") (pintype "bidirectional"))
    )
    (net (code "62") (name "RXIR") (class "Default")
      (node (ref "IC2") (pin "6") (pinfunction "IR_RXD_6") (pintype "bidirectional"))
      (node (ref "IC3") (pin "3") (pinfunction "RXD_3") (pintype "output"))
    )
    (net (code "63") (name "SCK") (class "Default")
      (node (ref "IC1") (pin "17") (pinfunction "PB5(SCK/PCINT5)_17") (pintype "bidirectional"))
      (node (ref "ISP1") (pin "3") (pinfunction "3_3") (pintype "passive"))
    )
    (net (code "64") (name "SCL") (class "Default")
      (node (ref "IC1") (pin "28") (pinfunction "PC5(ADC5/SCL/PCINT13)_28") (pintype "bidirectional"))
      (node (ref "IC4") (pin "10") (pinfunction "SCL_10") (pintype "input"))
      (node (ref "IC5") (pin "10") (pinfunction "SCL_10") (pintype "input"))
      (node (ref "R38") (pin "1") (pinfunction "1_1") (pintype "passive"))
    )
    (net (code "65") (name "SDA") (class "Default")
      (node (ref "IC1") (pin "27") (pinfunction "PC4(ADC4/SDA/PCINT12)_27") (pintype "bidirectional"))
      (node (ref "IC4") (pin "9") (pinfunction "SDA_9") (pintype "bidirectional"))
      (node (ref "IC5") (pin "9") (pinfunction "SDA_9") (pintype "bidirectional"))
      (node (ref "R37") (pin "1") (pinfunction "1_1") (pintype "passive"))
    )
    (net (code "66") (name "SENS_MOTL1") (class "Default")
      (node (ref "IC4") (pin "3") (pinfunction "OUT1_3") (pintype "output"))
      (node (ref "R33") (pin "1") (pinfunction "1_1") (pintype "passive"))
      (node (ref "R43") (pin "1") (pinfunction "1_1") (pintype "passive"))
    )
    (net (code "67") (name "SENS_MOTL2") (class "Default")
      (node (ref "MOT2") (pin "1") (pinfunction "P_1") (pintype "passive"))
      (node (ref "R33") (pin "2") (pinfunction "2_2") (pintype "passive"))
      (node (ref "R39") (pin "1") (pinfunction "1_1") (pintype "passive"))
    )
    (net (code "68") (name "SENS_MOTR1") (class "Default")
      (node (ref "IC5") (pin "3") (pinfunction "OUT1_3") (pintype "output"))
      (node (ref "R35") (pin "1") (pinfunction "1_1") (pintype "passive"))
      (node (ref "R45") (pin "1") (pinfunction "1_1") (pintype "passive"))
    )
    (net (code "69") (name "SENS_MOTR2") (class "Default")
      (node (ref "MOT4") (pin "1") (pinfunction "P_1") (pintype "passive"))
      (node (ref "R35") (pin "2") (pinfunction "2_2") (pintype "passive"))
      (node (ref "R41") (pin "1") (pinfunction "1_1") (pintype "passive"))
    )
    (net (code "70") (name "TXD") (class "Default")
      (node (ref "IC1") (pin "31") (pinfunction "PD1(TXD/PCINT17)_31") (pintype "bidirectional"))
      (node (ref "IC2") (pin "2") (pinfunction "TXD_2") (pintype "bidirectional"))
    )
    (net (code "71") (name "TXIR") (class "Default")
      (node (ref "IC2") (pin "7") (pinfunction "IR_TXD_7") (pintype "bidirectional"))
      (node (ref "IC3") (pin "2") (pinfunction "TXD_2") (pintype "input"))
    )
    (net (code "72") (name "VCC") (class "Default")
      (node (ref "C1") (pin "1") (pinfunction "1_1") (pintype "passive"))
      (node (ref "IC1") (pin "18") (pinfunction "AVCC_18") (pintype "passive"))
      (node (ref "IC1") (pin "4") (pinfunction "VCC_4") (pintype "power_in"))
      (node (ref "IC1") (pin "6") (pinfunction "VCC_6") (pintype "power_in"))
      (node (ref "IC2") (pin "8") (pinfunction "VCC_8") (pintype "bidirectional"))
      (node (ref "IC3") (pin "5") (pinfunction "VCC_5") (pintype "power_in"))
      (node (ref "IC4") (pin "4") (pinfunction "VCC_4") (pintype "power_in"))
      (node (ref "IC5") (pin "4") (pinfunction "VCC_4") (pintype "power_in"))
      (node (ref "IC5") (pin "7") (pinfunction "A0_7") (pintype "input"))
      (node (ref "ISP1") (pin "2") (pinfunction "2_2") (pintype "passive"))
      (node (ref "Q1") (pin "4") (pinfunction "VCC_4") (pintype "power_in"))
      (node (ref "Q5") (pin "C") (pinfunction "C_C") (pintype "passive"))
      (node (ref "Q6") (pin "C") (pinfunction "C_C") (pintype "passive"))
      (node (ref "Q7") (pin "C") (pinfunction "C_C") (pintype "passive"))
      (node (ref "Q8") (pin "C") (pinfunction "C_C") (pintype "passive"))
      (node (ref "R1") (pin "1") (pinfunction "1_1") (pintype "passive"))
      (node (ref "R2") (pin "1") (pinfunction "1_1") (pintype "passive"))
      (node (ref "R36") (pin "2") (pinfunction "2_2") (pintype "passive"))
      (node (ref "R37") (pin "2") (pinfunction "2_2") (pintype "passive"))
      (node (ref "R38") (pin "2") (pinfunction "2_2") (pintype "passive"))
      (node (ref "R5") (pin "1") (pinfunction "1_1") (pintype "passive"))
      (node (ref "S1") (pin "1") (pinfunction "1_1") (pintype "passive"))
      (node (ref "S1") (pin "2") (pinfunction "2_2") (pintype "passive"))
      (node (ref "U1") (pin "8") (pinfunction "V+_8") (pintype "power_in"))
    )
    (net (code "73") (name "unconnected-(IC1-ADC6-Pad19)") (class "Default")
      (node (ref "IC1") (pin "19") (pinfunction "ADC6_19") (pintype "passive"))
    )
    (net (code "74") (name "unconnected-(IC1-ADC7-Pad22)") (class "Default")
      (node (ref "IC1") (pin "22") (pinfunction "ADC7_22") (pintype "passive"))
    )
    (net (code "75") (name "unconnected-(IC1-PB7(XTAL2{slash}TOSC2{slash}PCINT7)-Pad8)") (class "Default")
      (node (ref "IC1") (pin "8") (pinfunction "PB7(XTAL2/TOSC2/PCINT7)_8") (pintype "bidirectional"))
    )
    (net (code "76") (name "unconnected-(IC1-PC2(ADC2{slash}PCINT10)-Pad25)") (class "Default")
      (node (ref "IC1") (pin "25") (pinfunction "PC2(ADC2/PCINT10)_25") (pintype "bidirectional"))
    )
    (net (code "77") (name "unconnected-(IC4-FAULTN-Pad6)") (class "Default")
      (node (ref "IC4") (pin "6") (pinfunction "FAULTN_6") (pintype "output"))
    )
    (net (code "78") (name "unconnected-(IC5-FAULTN-Pad6)") (class "Default")
      (node (ref "IC5") (pin "6") (pinfunction "FAULTN_6") (pintype "output"))
    )
  )
)
